# Microcontroller.net
KiCad netlist of a schematic drawn in Altium Designer
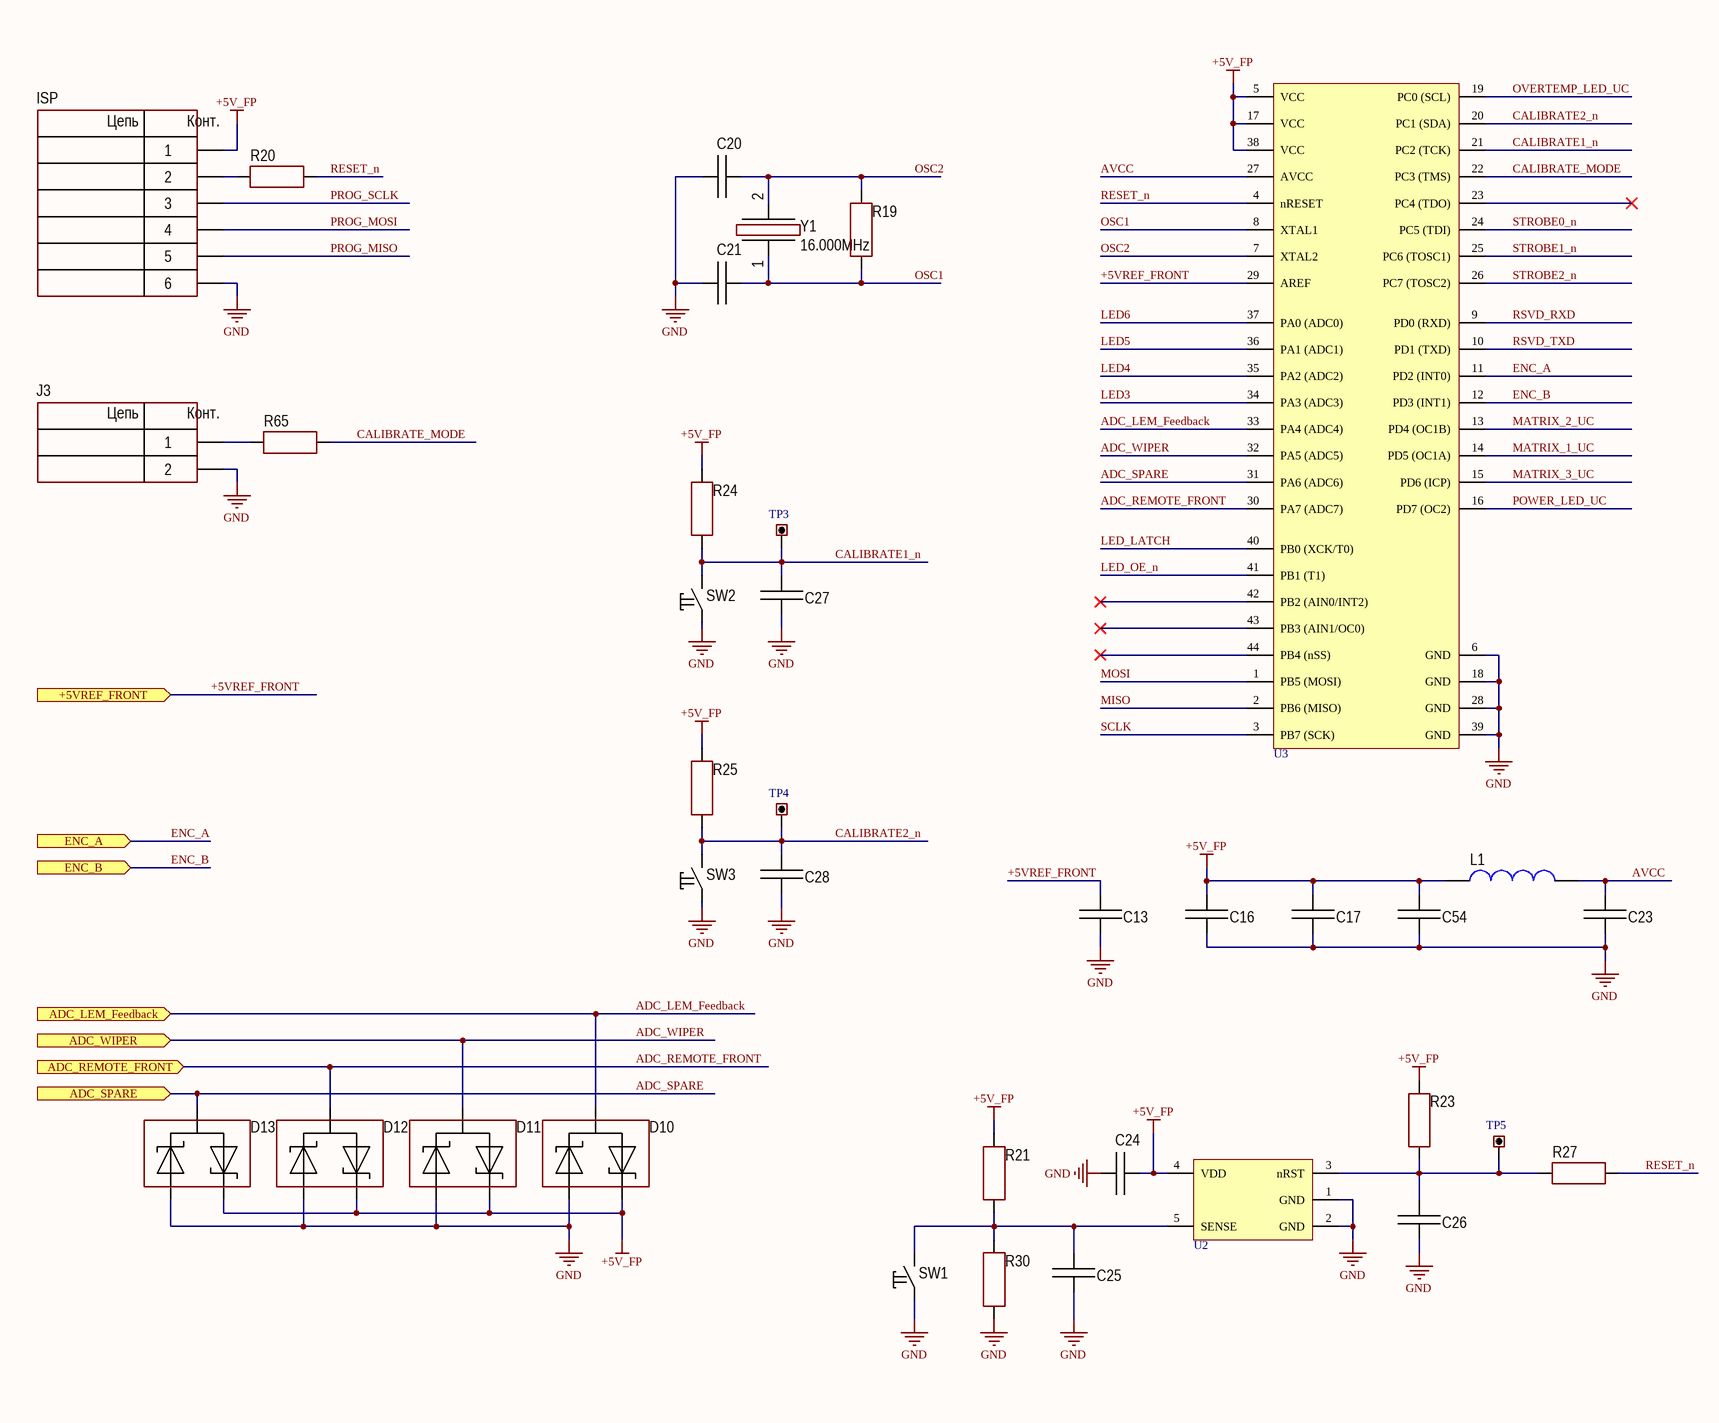
[diagram p0: Microcontroller.SchDoc, left]
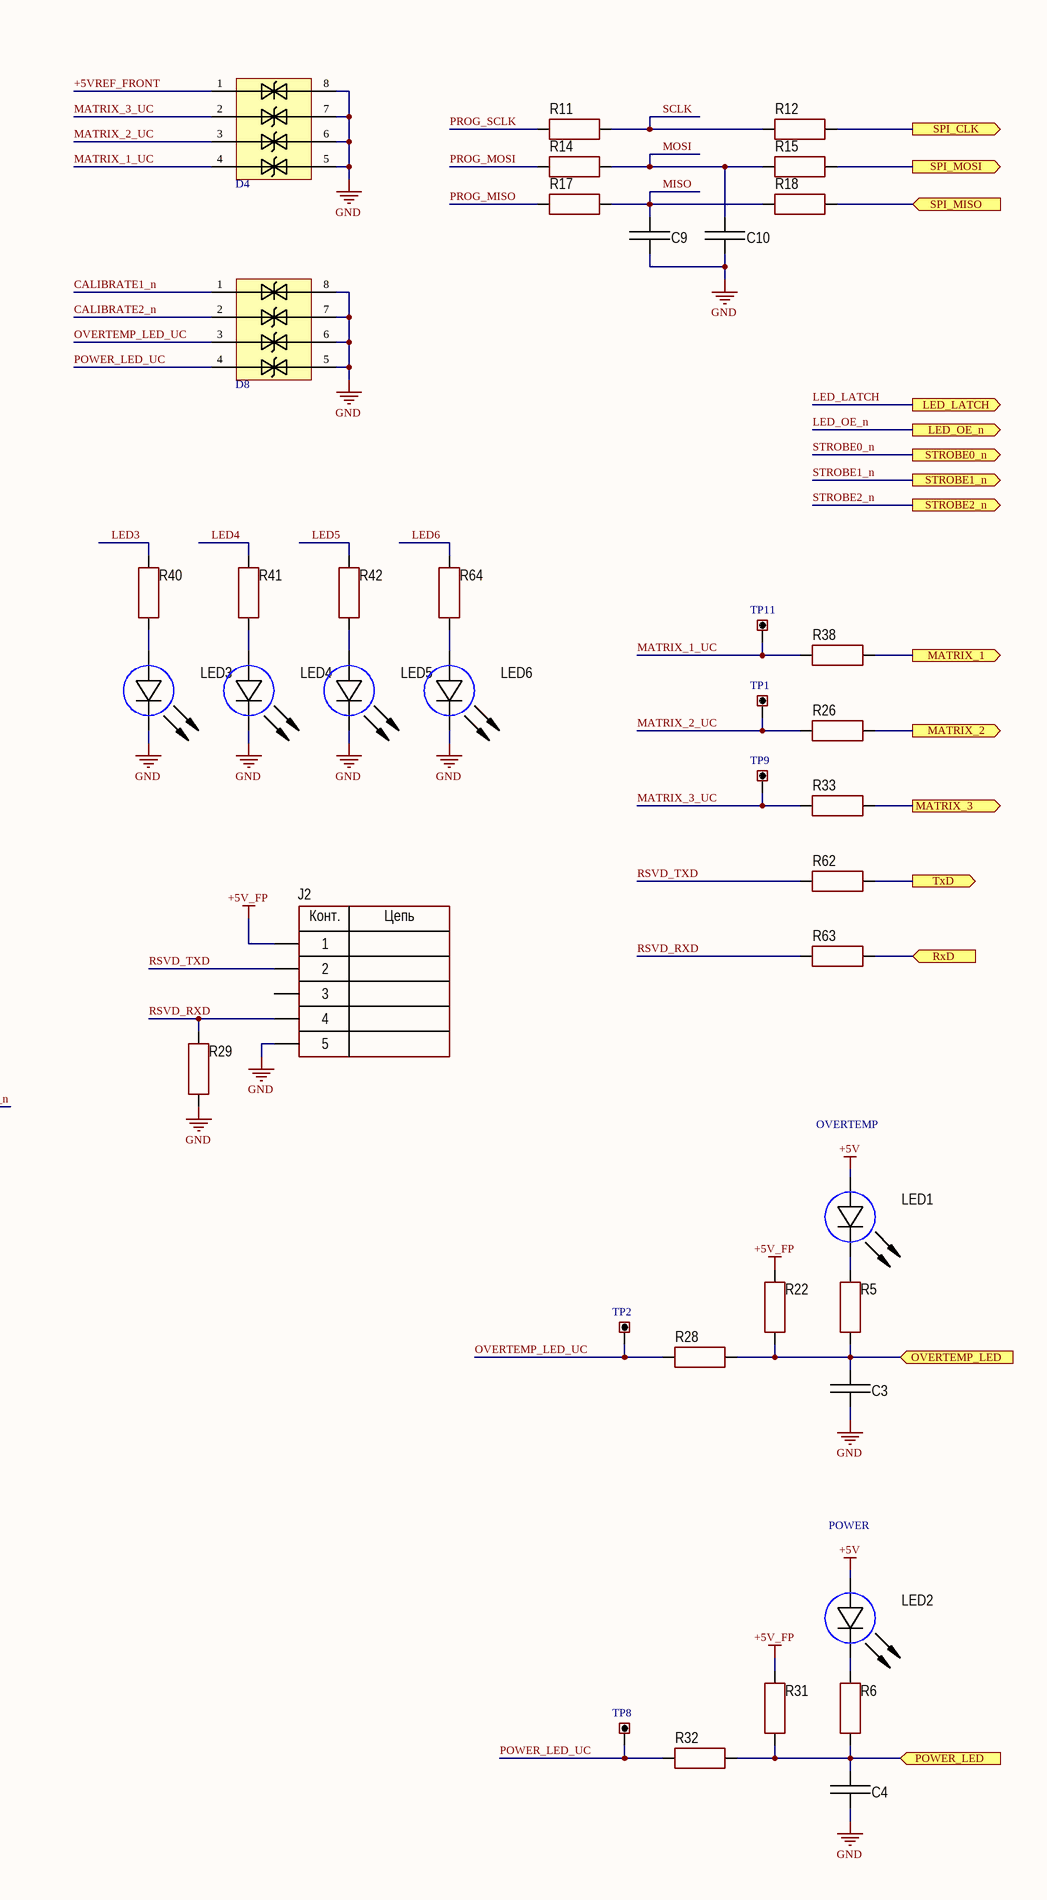
[diagram p1: Microcontroller.SchDoc, right]

(export (version "E")
  (design (tool "Eeschema 10.0.6"))
  (components
    (comp (ref "C3")
      (value "~")
      (footprint "StandardCase:CAP: 1206")
      (fields
        (field (name "MANUFACTURER") "Yageo")
        (field (name "PARTNUMBER") "CC1206KRX7R9BB104")
        (field (name "VALUEMANUFACTURERPARTNUMBER") "Ceramic capacitor, 0.1μF, 1206")
      )
      (libsource (lib "Capacitor") (part "Ceramic_1206"))
    )
    (comp (ref "C4")
      (value "~")
      (footprint "StandardCase:CAP: 1206")
      (fields
        (field (name "MANUFACTURER") "Yageo")
        (field (name "PARTNUMBER") "CC1206KRX7R9BB104")
        (field (name "VALUEMANUFACTURERPARTNUMBER") "Ceramic capacitor, 0.1μF, 1206")
      )
      (libsource (lib "Capacitor") (part "Ceramic_1206"))
    )
    (comp (ref "C9")
      (value "~")
      (footprint "StandardCase:CAP: 1206")
      (fields
        (field (name "MANUFACTURER") "Yageo")
        (field (name "PARTNUMBER") "CC1206KRX7R9BB104")
        (field (name "VALUEMANUFACTURERPARTNUMBER") "Ceramic capacitor, 10nF, 1206")
      )
      (libsource (lib "Capacitor") (part "Ceramic_1206"))
    )
    (comp (ref "C10")
      (value "~")
      (footprint "StandardCase:CAP: 1206")
      (fields
        (field (name "MANUFACTURER") "Yageo")
        (field (name "PARTNUMBER") "CC1206KRX7R9BB104")
        (field (name "VALUEMANUFACTURERPARTNUMBER") "Ceramic capacitor, 10nF, 1206")
      )
      (libsource (lib "Capacitor") (part "Ceramic_1206"))
    )
    (comp (ref "C13")
      (value "~")
      (footprint "StandardCase:CAP: 1206")
      (fields
        (field (name "MANUFACTURER") "Yageo")
        (field (name "PARTNUMBER") "CC1206KRX7R9BB104")
        (field (name "VALUEMANUFACTURERPARTNUMBER") "Ceramic capacitor, 0.1μF, 1206")
      )
      (libsource (lib "Capacitor") (part "Ceramic_1206"))
    )
    (comp (ref "C16")
      (value "~")
      (footprint "StandardCase:CAP: 1206")
      (fields
        (field (name "MANUFACTURER") "Yageo")
        (field (name "PARTNUMBER") "CC1206KRX7R9BB104")
        (field (name "VALUEMANUFACTURERPARTNUMBER") "Ceramic capacitor, 0.1μF, 1206")
      )
      (libsource (lib "Capacitor") (part "Ceramic_1206"))
    )
    (comp (ref "C17")
      (value "~")
      (footprint "StandardCase:CAP: 1206")
      (fields
        (field (name "MANUFACTURER") "Yageo")
        (field (name "PARTNUMBER") "CC1206KRX7R9BB104")
        (field (name "VALUEMANUFACTURERPARTNUMBER") "Ceramic capacitor, 0.1μF, 1206")
      )
      (libsource (lib "Capacitor") (part "Ceramic_1206"))
    )
    (comp (ref "C20")
      (value "~")
      (footprint "StandardCase:CAP: 1206")
      (fields
        (field (name "MANUFACTURER") "Yageo")
        (field (name "PARTNUMBER") "CC1206KRX7R9BB104")
        (field (name "VALUEMANUFACTURERPARTNUMBER") "Ceramic capacitor, 22pF, 1206")
      )
      (libsource (lib "Capacitor") (part "Ceramic_1206"))
    )
    (comp (ref "C21")
      (value "~")
      (footprint "StandardCase:CAP: 1206")
      (fields
        (field (name "MANUFACTURER") "Yageo")
        (field (name "PARTNUMBER") "CC1206KRX7R9BB104")
        (field (name "VALUEMANUFACTURERPARTNUMBER") "Ceramic capacitor, 22pF, 1206")
      )
      (libsource (lib "Capacitor") (part "Ceramic_1206"))
    )
    (comp (ref "C23")
      (value "~")
      (footprint "StandardCase:CAP: 1206")
      (fields
        (field (name "MANUFACTURER") "Yageo")
        (field (name "PARTNUMBER") "CC1206KRX7R9BB104")
        (field (name "VALUEMANUFACTURERPARTNUMBER") "Ceramic capacitor, 1.0μF, 1206")
      )
      (libsource (lib "Capacitor") (part "Ceramic_1206"))
    )
    (comp (ref "C24")
      (value "~")
      (footprint "StandardCase:CAP: 1206")
      (fields
        (field (name "MANUFACTURER") "Yageo")
        (field (name "PARTNUMBER") "CC1206KRX7R9BB104")
        (field (name "VALUEMANUFACTURERPARTNUMBER") "Ceramic capacitor, 10nF, 1206")
      )
      (libsource (lib "Capacitor") (part "Ceramic_1206"))
    )
    (comp (ref "C25")
      (value "~")
      (footprint "StandardCase:CAP: 1206")
      (fields
        (field (name "MANUFACTURER") "Yageo")
        (field (name "PARTNUMBER") "CC1206KRX7R9BB104")
        (field (name "VALUEMANUFACTURERPARTNUMBER") "Ceramic capacitor, 10nF, 1206")
      )
      (libsource (lib "Capacitor") (part "Ceramic_1206"))
    )
    (comp (ref "C26")
      (value "~")
      (footprint "StandardCase:CAP: 1206")
      (fields
        (field (name "MANUFACTURER") "Yageo")
        (field (name "PARTNUMBER") "CC1206KRX7R9BB104")
        (field (name "VALUEMANUFACTURERPARTNUMBER") "Ceramic capacitor, 0.1μF, 1206")
      )
      (libsource (lib "Capacitor") (part "Ceramic_1206"))
    )
    (comp (ref "C27")
      (value "~")
      (footprint "StandardCase:CAP: 1206")
      (fields
        (field (name "MANUFACTURER") "Yageo")
        (field (name "PARTNUMBER") "CC1206KRX7R9BB104")
        (field (name "VALUEMANUFACTURERPARTNUMBER") "Ceramic capacitor, 0.1μF, 1206")
      )
      (libsource (lib "Capacitor") (part "Ceramic_1206"))
    )
    (comp (ref "C28")
      (value "~")
      (footprint "StandardCase:CAP: 1206")
      (fields
        (field (name "MANUFACTURER") "Yageo")
        (field (name "PARTNUMBER") "CC1206KRX7R9BB104")
        (field (name "VALUEMANUFACTURERPARTNUMBER") "Ceramic capacitor, 0.1μF, 1206")
      )
      (libsource (lib "Capacitor") (part "Ceramic_1206"))
    )
    (comp (ref "C54")
      (value "~")
      (footprint "StandardCase:CAP: 1206")
      (fields
        (field (name "MANUFACTURER") "Yageo")
        (field (name "PARTNUMBER") "CC1206KRX7R9BB104")
        (field (name "VALUEMANUFACTURERPARTNUMBER") "Ceramic capacitor, 0.1μF, 1206")
      )
      (libsource (lib "Capacitor") (part "Ceramic_1206"))
    )
    (comp (ref "D4")
      (value "~")
      (footprint "StandardCase:8-SOIC")
      (fields
        (field (name "VALUEMANUFACTURERPARTNUMBER") "CDNBS08-T05C, SOIC-8")
        (field (name "PARTNUMBER") "CDNBS08-T05C")
      )
      (libsource (lib "FP_lib_SCH") (part "CDNBS08-T05C"))
    )
    (comp (ref "D8")
      (value "~")
      (footprint "StandardCase:8-SOIC")
      (fields
        (field (name "VALUEMANUFACTURERPARTNUMBER") "CDNBS08-T05C, SOIC-8")
        (field (name "PARTNUMBER") "CDNBS08-T05C")
      )
      (libsource (lib "FP_lib_SCH") (part "CDNBS08-T05C"))
    )
    (comp (ref "D10")
      (value "~")
      (footprint "StandardCase:SOT23")
      (fields
        (field (name "MANUFACTURER") "Diodes Incorporated")
        (field (name "VALUEMANUFACTURERPARTNUMBER") "BAS40-04, SOT23-3")
        (field (name "VOLTAGE") "40V")
      )
      (libsource (lib "Diode") (part "Schottky_array"))
    )
    (comp (ref "D11")
      (value "~")
      (footprint "StandardCase:SOT23")
      (fields
        (field (name "MANUFACTURER") "Diodes Incorporated")
        (field (name "VALUEMANUFACTURERPARTNUMBER") "BAS40-04, SOT23-3")
        (field (name "VOLTAGE") "40V")
      )
      (libsource (lib "Diode") (part "Schottky_array"))
    )
    (comp (ref "D12")
      (value "~")
      (footprint "StandardCase:SOT23")
      (fields
        (field (name "MANUFACTURER") "Diodes Incorporated")
        (field (name "VALUEMANUFACTURERPARTNUMBER") "BAS40-04, SOT23-3")
        (field (name "VOLTAGE") "40V")
      )
      (libsource (lib "Diode") (part "Schottky_array"))
    )
    (comp (ref "D13")
      (value "~")
      (footprint "StandardCase:SOT23")
      (fields
        (field (name "MANUFACTURER") "Diodes Incorporated")
        (field (name "VALUEMANUFACTURERPARTNUMBER") "BAS40-04, SOT23-3")
        (field (name "VOLTAGE") "40V")
      )
      (libsource (lib "Diode") (part "Schottky_array"))
    )
    (comp (ref "ISP")
      (value "~")
      (footprint "CustomCase:CON: PLS-6")
      (fields
        (field (name "MANUFACTURER") "Connfly")
        (field (name "VALUEMANUFACTURERPARTNUMBER") "Connector, PLS-6, 6 pin")
        (field (name "PARTNUMBER") "PLS-6")
      )
      (libsource (lib "Connector") (part "PLS-6"))
    )
    (comp (ref "J2")
      (value "~")
      (footprint "CustomCase:CON: PLS-5")
      (fields
        (field (name "MANUFACTURER") "Connfly")
        (field (name "VALUEMANUFACTURERPARTNUMBER") "Connector, PBS-5, 5 pin")
        (field (name "PARTNUMBER") "PBS-5")
      )
      (libsource (lib "Connector") (part "PBS-5"))
    )
    (comp (ref "J3")
      (value "~")
      (footprint "CustomCase:CON: PLS-2")
      (fields
        (field (name "MANUFACTURER") "Connfly")
        (field (name "VALUEMANUFACTURERPARTNUMBER") "PLS-2, 2pin")
        (field (name "PARTNUMBER") "PLS-2")
      )
      (libsource (lib "Connector") (part "PLS-2"))
    )
    (comp (ref "L1")
      (value "~")
      (footprint "StandardCase:RES: 1206")
      (fields
        (field (name "MANUFACTURER") "Murata Electronics")
        (field (name "PARTNUMBER") "LQM21FN100M70L")
        (field (name "VALUEMANUFACTURERPARTNUMBER") "Fixed inductor, 100μH, 1206")
      )
      (libsource (lib "Inductor") (part "Inductor_0805"))
    )
    (comp (ref "LED1")
      (value "~")
      (footprint "CustomCase:DIODE: LED5MM_Y")
      (fields (field (name "VALUEMANUFACTURERPARTNUMBER") "LED, YELLOW, 5 mm"))
      (libsource (lib "Diode") (part "LED_single"))
    )
    (comp (ref "LED2")
      (value "~")
      (footprint "CustomCase:DIODE: LED5MM_G")
      (fields (field (name "VALUEMANUFACTURERPARTNUMBER") "LED, BLUE, 5 mm"))
      (libsource (lib "Diode") (part "LED_single"))
    )
    (comp (ref "LED3")
      (value "~")
      (footprint "CustomCase:DIODE: LED5MM_G")
      (fields (field (name "VALUEMANUFACTURERPARTNUMBER") "LED, GREEN, 5 mm"))
      (libsource (lib "Diode") (part "LED_single"))
    )
    (comp (ref "LED4")
      (value "~")
      (footprint "CustomCase:DIODE: LED5MM_G")
      (fields (field (name "VALUEMANUFACTURERPARTNUMBER") "LED, GREEN, 5 mm"))
      (libsource (lib "Diode") (part "LED_single"))
    )
    (comp (ref "LED5")
      (value "~")
      (footprint "CustomCase:DIODE: LED5MM_G")
      (fields (field (name "VALUEMANUFACTURERPARTNUMBER") "LED, GREEN, 5 mm"))
      (libsource (lib "Diode") (part "LED_single"))
    )
    (comp (ref "LED6")
      (value "~")
      (footprint "CustomCase:DIODE: LED5MM_G")
      (fields (field (name "VALUEMANUFACTURERPARTNUMBER") "LED, GREEN, 5 mm"))
      (libsource (lib "Diode") (part "LED_single"))
    )
    (comp (ref "R5")
      (value "~")
      (footprint "StandardCase:RES: 1206")
      (fields
        (field (name "MANUFACTURER") "Yageo")
        (field (name "PARTNUMBER") "RC1206JR-07100RL")
        (field (name "VALUEMANUFACTURERPARTNUMBER") "Resistor, 2K, 1206")
      )
      (libsource (lib "") (part "Resistor_1206_2"))
    )
    (comp (ref "R6")
      (value "~")
      (footprint "StandardCase:RES: 1206")
      (fields
        (field (name "MANUFACTURER") "Yageo")
        (field (name "PARTNUMBER") "RC1206JR-07100RL")
        (field (name "VALUEMANUFACTURERPARTNUMBER") "Resistor, 2K, 1206")
      )
      (libsource (lib "") (part "Resistor_1206_2"))
    )
    (comp (ref "R11")
      (value "~")
      (footprint "StandardCase:RES: 1206")
      (fields
        (field (name "MANUFACTURER") "Yageo")
        (field (name "PARTNUMBER") "RC1206JR-07100RL")
        (field (name "VALUEMANUFACTURERPARTNUMBER") "Resistor, 47R, 1206")
      )
      (libsource (lib "Resistor") (part "Resistor_1206"))
    )
    (comp (ref "R12")
      (value "~")
      (footprint "StandardCase:RES: 1206")
      (fields
        (field (name "MANUFACTURER") "Yageo")
        (field (name "PARTNUMBER") "RC1206JR-07100RL")
        (field (name "VALUEMANUFACTURERPARTNUMBER") "Resistor, 47R, 1206")
      )
      (libsource (lib "Resistor") (part "Resistor_1206"))
    )
    (comp (ref "R14")
      (value "~")
      (footprint "StandardCase:RES: 1206")
      (fields
        (field (name "MANUFACTURER") "Yageo")
        (field (name "PARTNUMBER") "RC1206JR-07100RL")
        (field (name "VALUEMANUFACTURERPARTNUMBER") "Resistor, 47R, 1206")
      )
      (libsource (lib "Resistor") (part "Resistor_1206"))
    )
    (comp (ref "R15")
      (value "~")
      (footprint "StandardCase:RES: 1206")
      (fields
        (field (name "MANUFACTURER") "Yageo")
        (field (name "PARTNUMBER") "RC1206JR-07100RL")
        (field (name "VALUEMANUFACTURERPARTNUMBER") "Resistor, 47R, 1206")
      )
      (libsource (lib "Resistor") (part "Resistor_1206"))
    )
    (comp (ref "R17")
      (value "~")
      (footprint "StandardCase:RES: 1206")
      (fields
        (field (name "MANUFACTURER") "Yageo")
        (field (name "PARTNUMBER") "RC1206JR-07100RL")
        (field (name "VALUEMANUFACTURERPARTNUMBER") "Resistor, 47R, 1206")
      )
      (libsource (lib "Resistor") (part "Resistor_1206"))
    )
    (comp (ref "R18")
      (value "~")
      (footprint "StandardCase:RES: 1206")
      (fields
        (field (name "MANUFACTURER") "Yageo")
        (field (name "PARTNUMBER") "RC1206JR-07100RL")
        (field (name "VALUEMANUFACTURERPARTNUMBER") "Resistor, 47R, 1206")
      )
      (libsource (lib "Resistor") (part "Resistor_1206"))
    )
    (comp (ref "R19")
      (value "~")
      (footprint "StandardCase:RES: 1206")
      (fields
        (field (name "MANUFACTURER") "Yageo")
        (field (name "PARTNUMBER") "RC1206JR-07100RL")
        (field (name "VALUEMANUFACTURERPARTNUMBER") "Resistor, 1M, 1206")
      )
      (libsource (lib "") (part "Resistor_1206_1"))
    )
    (comp (ref "R20")
      (value "~")
      (footprint "StandardCase:RES: 1206")
      (fields
        (field (name "MANUFACTURER") "Yageo")
        (field (name "PARTNUMBER") "RC1206JR-07100RL")
        (field (name "VALUEMANUFACTURERPARTNUMBER") "Resistor, 47R, 1206")
      )
      (libsource (lib "Resistor") (part "Resistor_1206"))
    )
    (comp (ref "R21")
      (value "~")
      (footprint "StandardCase:RES: 1206")
      (fields
        (field (name "MANUFACTURER") "Yageo")
        (field (name "PARTNUMBER") "RC1206JR-07100RL")
        (field (name "VALUEMANUFACTURERPARTNUMBER") "Resistor, 10K, 1206")
      )
      (libsource (lib "") (part "Resistor_1206_1"))
    )
    (comp (ref "R22")
      (value "~")
      (footprint "StandardCase:RES: 1206")
      (fields
        (field (name "MANUFACTURER") "Yageo")
        (field (name "PARTNUMBER") "RC1206JR-07100RL")
        (field (name "VALUEMANUFACTURERPARTNUMBER") "Resistor, 10K, 1206")
      )
      (libsource (lib "") (part "Resistor_1206_2"))
    )
    (comp (ref "R23")
      (value "~")
      (footprint "StandardCase:RES: 1206")
      (fields
        (field (name "MANUFACTURER") "Yageo")
        (field (name "PARTNUMBER") "RC1206JR-07100RL")
        (field (name "VALUEMANUFACTURERPARTNUMBER") "Resistor, 10K, 1206")
      )
      (libsource (lib "") (part "Resistor_1206_1"))
    )
    (comp (ref "R24")
      (value "~")
      (footprint "StandardCase:RES: 1206")
      (fields
        (field (name "MANUFACTURER") "Yageo")
        (field (name "PARTNUMBER") "RC1206JR-07100RL")
        (field (name "VALUEMANUFACTURERPARTNUMBER") "Resistor, 10K, 1206")
      )
      (libsource (lib "") (part "Resistor_1206_1"))
    )
    (comp (ref "R25")
      (value "~")
      (footprint "StandardCase:RES: 1206")
      (fields
        (field (name "MANUFACTURER") "Yageo")
        (field (name "PARTNUMBER") "RC1206JR-07100RL")
        (field (name "VALUEMANUFACTURERPARTNUMBER") "Resistor, 10K, 1206")
      )
      (libsource (lib "") (part "Resistor_1206_1"))
    )
    (comp (ref "R26")
      (value "~")
      (footprint "StandardCase:RES: 1206")
      (fields
        (field (name "MANUFACTURER") "Yageo")
        (field (name "PARTNUMBER") "RC1206JR-07100RL")
        (field (name "VALUEMANUFACTURERPARTNUMBER") "Resistor, 1K, 1206")
      )
      (libsource (lib "") (part "Resistor_1206_3"))
    )
    (comp (ref "R27")
      (value "~")
      (footprint "StandardCase:RES: 1206")
      (fields
        (field (name "MANUFACTURER") "Yageo")
        (field (name "PARTNUMBER") "RC1206JR-07100RL")
        (field (name "VALUEMANUFACTURERPARTNUMBER") "Resistor, 47R, 1206")
      )
      (libsource (lib "Resistor") (part "Resistor_1206"))
    )
    (comp (ref "R28")
      (value "~")
      (footprint "StandardCase:RES: 1206")
      (fields
        (field (name "MANUFACTURER") "Yageo")
        (field (name "PARTNUMBER") "RC1206JR-07100RL")
        (field (name "VALUEMANUFACTURERPARTNUMBER") "Resistor, 1K, 1206")
      )
      (libsource (lib "Resistor") (part "Resistor_1206"))
    )
    (comp (ref "R29")
      (value "~")
      (footprint "StandardCase:RES: 1206")
      (fields
        (field (name "MANUFACTURER") "Yageo")
        (field (name "PARTNUMBER") "RC1206JR-07100RL")
        (field (name "VALUEMANUFACTURERPARTNUMBER") "Resistor, 10K, 1206")
      )
      (libsource (lib "") (part "Resistor_1206_1"))
    )
    (comp (ref "R30")
      (value "~")
      (footprint "StandardCase:RES: 1206")
      (fields
        (field (name "MANUFACTURER") "Yageo")
        (field (name "PARTNUMBER") "RC1206JR-07100RL")
        (field (name "VALUEMANUFACTURERPARTNUMBER") "Resistor, 4.32K, 1206")
      )
      (libsource (lib "") (part "Resistor_1206_1"))
    )
    (comp (ref "R31")
      (value "~")
      (footprint "StandardCase:RES: 1206")
      (fields
        (field (name "MANUFACTURER") "Yageo")
        (field (name "PARTNUMBER") "RC1206JR-07100RL")
        (field (name "VALUEMANUFACTURERPARTNUMBER") "Resistor, 10K, 1206")
      )
      (libsource (lib "") (part "Resistor_1206_2"))
    )
    (comp (ref "R32")
      (value "~")
      (footprint "StandardCase:RES: 1206")
      (fields
        (field (name "MANUFACTURER") "Yageo")
        (field (name "PARTNUMBER") "RC1206JR-07100RL")
        (field (name "VALUEMANUFACTURERPARTNUMBER") "Resistor, 1K, 1206")
      )
      (libsource (lib "") (part "Resistor_1206_3"))
    )
    (comp (ref "R33")
      (value "~")
      (footprint "StandardCase:RES: 1206")
      (fields
        (field (name "MANUFACTURER") "Yageo")
        (field (name "PARTNUMBER") "RC1206JR-07100RL")
        (field (name "VALUEMANUFACTURERPARTNUMBER") "Resistor, 1K, 1206")
      )
      (libsource (lib "") (part "Resistor_1206_3"))
    )
    (comp (ref "R38")
      (value "~")
      (footprint "StandardCase:RES: 1206")
      (fields
        (field (name "MANUFACTURER") "Yageo")
        (field (name "PARTNUMBER") "RC1206JR-07100RL")
        (field (name "VALUEMANUFACTURERPARTNUMBER") "Resistor, 1K, 1206")
      )
      (libsource (lib "") (part "Resistor_1206_3"))
    )
    (comp (ref "R40")
      (value "~")
      (footprint "StandardCase:RES: 1206")
      (fields
        (field (name "MANUFACTURER") "Yageo")
        (field (name "PARTNUMBER") "RC1206JR-07100RL")
        (field (name "VALUEMANUFACTURERPARTNUMBER") "Resistor, 2K, 1206")
      )
      (libsource (lib "") (part "Resistor_1206_2"))
    )
    (comp (ref "R41")
      (value "~")
      (footprint "StandardCase:RES: 1206")
      (fields
        (field (name "MANUFACTURER") "Yageo")
        (field (name "PARTNUMBER") "RC1206JR-07100RL")
        (field (name "VALUEMANUFACTURERPARTNUMBER") "Resistor, 2K, 1206")
      )
      (libsource (lib "") (part "Resistor_1206_2"))
    )
    (comp (ref "R42")
      (value "~")
      (footprint "StandardCase:RES: 1206")
      (fields
        (field (name "MANUFACTURER") "Yageo")
        (field (name "PARTNUMBER") "RC1206JR-07100RL")
        (field (name "VALUEMANUFACTURERPARTNUMBER") "Resistor, 2K, 1206")
      )
      (libsource (lib "") (part "Resistor_1206_2"))
    )
    (comp (ref "R62")
      (value "~")
      (footprint "StandardCase:RES: 1206")
      (fields
        (field (name "MANUFACTURER") "Yageo")
        (field (name "PARTNUMBER") "RC1206JR-07100RL")
        (field (name "VALUEMANUFACTURERPARTNUMBER") "Resistor, 1K, 1206")
      )
      (libsource (lib "") (part "Resistor_1206_3"))
    )
    (comp (ref "R63")
      (value "~")
      (footprint "StandardCase:RES: 1206")
      (fields
        (field (name "MANUFACTURER") "Yageo")
        (field (name "PARTNUMBER") "RC1206JR-07100RL")
        (field (name "VALUEMANUFACTURERPARTNUMBER") "Resistor, 1K, 1206")
      )
      (libsource (lib "") (part "Resistor_1206_3"))
    )
    (comp (ref "R64")
      (value "~")
      (footprint "StandardCase:RES: 1206")
      (fields
        (field (name "MANUFACTURER") "Yageo")
        (field (name "PARTNUMBER") "RC1206JR-07100RL")
        (field (name "VALUEMANUFACTURERPARTNUMBER") "Resistor, 2K, 1206")
      )
      (libsource (lib "") (part "Resistor_1206_2"))
    )
    (comp (ref "R65")
      (value "~")
      (footprint "StandardCase:RES: 1206")
      (fields
        (field (name "MANUFACTURER") "Yageo")
        (field (name "PARTNUMBER") "RC1206JR-07100RL")
        (field (name "VALUEMANUFACTURERPARTNUMBER") "Resistor, 1K, 1206")
      )
      (libsource (lib "Resistor") (part "Resistor_1206"))
    )
    (comp (ref "SW1")
      (value "~")
      (footprint "FP_lib_PCB:DTSM-32")
      (fields
        (field (name "MANUFACTURER") "TE Connectivity")
        (field (name "VALUEMANUFACTURERPARTNUMBER") "Tactile button, DTSM-32")
        (field (name "PARTNUMBER") "DTSM-32")
      )
      (libsource (lib "Electromechanics") (part "Button_tactile"))
    )
    (comp (ref "SW2")
      (value "~")
      (footprint "FP_lib_PCB:DTSM-32")
      (fields
        (field (name "MANUFACTURER") "TE Connectivity")
        (field (name "VALUEMANUFACTURERPARTNUMBER") "Tactile button, DTSM-32")
        (field (name "PARTNUMBER") "DTSM-32")
      )
      (libsource (lib "Electromechanics") (part "Button_tactile"))
    )
    (comp (ref "SW3")
      (value "~")
      (footprint "FP_lib_PCB:DTSM-32")
      (fields
        (field (name "MANUFACTURER") "TE Connectivity")
        (field (name "VALUEMANUFACTURERPARTNUMBER") "Tactile button, DTSM-32")
        (field (name "PARTNUMBER") "DTSM-32")
      )
      (libsource (lib "Electromechanics") (part "Button_tactile"))
    )
    (comp (ref "TP1")
      (value "Test_Point")
      (footprint "FP_lib_PCB:Test_Point")
      (libsource (lib "FP_lib_SCH") (part "Test_Point"))
    )
    (comp (ref "TP2")
      (value "Test_Point")
      (footprint "FP_lib_PCB:Test_Point")
      (libsource (lib "FP_lib_SCH") (part "Test_Point"))
    )
    (comp (ref "TP3")
      (value "Test_Point")
      (footprint "FP_lib_PCB:Test_Point")
      (libsource (lib "FP_lib_SCH") (part "Test_Point"))
    )
    (comp (ref "TP4")
      (value "Test_Point")
      (footprint "FP_lib_PCB:Test_Point")
      (libsource (lib "FP_lib_SCH") (part "Test_Point"))
    )
    (comp (ref "TP5")
      (value "Test_Point")
      (footprint "FP_lib_PCB:Test_Point")
      (libsource (lib "FP_lib_SCH") (part "Test_Point"))
    )
    (comp (ref "TP8")
      (value "Test_Point")
      (footprint "FP_lib_PCB:Test_Point")
      (libsource (lib "FP_lib_SCH") (part "Test_Point"))
    )
    (comp (ref "TP9")
      (value "Test_Point")
      (footprint "FP_lib_PCB:Test_Point")
      (libsource (lib "FP_lib_SCH") (part "Test_Point"))
    )
    (comp (ref "TP11")
      (value "Test_Point")
      (footprint "FP_lib_PCB:Test_Point")
      (libsource (lib "FP_lib_SCH") (part "Test_Point"))
    )
    (comp (ref "U2")
      (value "~")
      (footprint "FP_lib_PCB:TPS3801")
      (fields
        (field (name "VALUEMANUFACTURERPARTNUMBER") "TPS3801, SOT23-5")
        (field (name "PARTNUMBER") "TPS3801")
      )
      (libsource (lib "FP_lib_SCH") (part "TPS3801"))
    )
    (comp (ref "U3")
      (value "~")
      (footprint "FP_lib_PCB:TQFP80P1200X1200X120-44L")
      (fields
        (field (name "VALUEMANUFACTURERPARTNUMBER") "ATMega16-16AU, TQFP-44")
        (field (name "PARTNUMBER") "ATMega16-16AU")
      )
      (libsource (lib "FP_lib_SCH") (part "ATMega16-16AU"))
    )
    (comp (ref "Y1")
      (value "~")
      (footprint "FP_lib_PCB:HC49SM")
      (fields
        (field (name "MANUFACTURER") "Epson")
        (field (name "PARTNUMBER") "HC49SM-16.000MHZ-20PF")
        (field (name "VALUEMANUFACTURERPARTNUMBER") "HC49SM-16.000MHZ-20PF, HC49SM")
        (field (name "FREQUENCY") "16.000MHz")
      )
      (libsource (lib "Oscilator") (part "Crystal_3215"))
    )
  )
  (nets
    (net (code "1") (name "+5V") (class "Default")
      (node (ref "LED1") (pin "1") (pinfunction "A_1") (pintype "passive"))
      (node (ref "LED2") (pin "1") (pinfunction "A_1") (pintype "passive"))
    )
    (net (code "2") (name "+5V_FP") (class "Default")
      (node (ref "C16") (pin "2") (pinfunction "2_2") (pintype "power_in"))
      (node (ref "C17") (pin "2") (pinfunction "2_2") (pintype "power_in"))
      (node (ref "C24") (pin "2") (pinfunction "2_2") (pintype "power_in"))
      (node (ref "C54") (pin "2") (pinfunction "2_2") (pintype "power_in"))
      (node (ref "D10") (pin "2") (pinfunction "2_2") (pintype "passive"))
      (node (ref "D11") (pin "2") (pinfunction "2_2") (pintype "passive"))
      (node (ref "D12") (pin "2") (pinfunction "2_2") (pintype "passive"))
      (node (ref "D13") (pin "2") (pinfunction "2_2") (pintype "passive"))
      (node (ref "ISP") (pin "1") (pinfunction "1_1") (pintype "passive"))
      (node (ref "J2") (pin "1") (pinfunction "1_1") (pintype "passive"))
      (node (ref "L1") (pin "2") (pinfunction "2_2") (pintype "passive"))
      (node (ref "R21") (pin "1") (pinfunction "1_1") (pintype "passive"))
      (node (ref "R22") (pin "2") (pinfunction "2_2") (pintype "passive"))
      (node (ref "R23") (pin "1") (pinfunction "1_1") (pintype "passive"))
      (node (ref "R24") (pin "1") (pinfunction "1_1") (pintype "passive"))
      (node (ref "R25") (pin "1") (pinfunction "1_1") (pintype "passive"))
      (node (ref "R31") (pin "2") (pinfunction "2_2") (pintype "passive"))
      (node (ref "U2") (pin "4") (pinfunction "VDD_4") (pintype "passive"))
      (node (ref "U3") (pin "17") (pinfunction "VCC_17") (pintype "passive"))
      (node (ref "U3") (pin "38") (pinfunction "VCC_38") (pintype "passive"))
      (node (ref "U3") (pin "5") (pinfunction "VCC_5") (pintype "passive"))
    )
    (net (code "3") (name "/+5VREF_FRONT") (class "Default")
      (node (ref "C13") (pin "2") (pinfunction "2_2") (pintype "power_in"))
      (node (ref "D4") (pin "1") (pintype "passive"))
      (node (ref "U3") (pin "29") (pinfunction "AREF_29") (pintype "passive"))
    )
    (net (code "4") (name "/ADC_LEM_Feedback") (class "Default")
      (node (ref "D10") (pin "3") (pinfunction "3_3") (pintype "passive"))
      (node (ref "U3") (pin "33") (pinfunction "PA4_(ADC4)_33") (pintype "passive"))
    )
    (net (code "5") (name "/ADC_REMOTE_FRONT") (class "Default")
      (node (ref "D12") (pin "3") (pinfunction "3_3") (pintype "passive"))
      (node (ref "U3") (pin "30") (pinfunction "PA7_(ADC7)_30") (pintype "passive"))
    )
    (net (code "6") (name "/ADC_SPARE") (class "Default")
      (node (ref "D13") (pin "3") (pinfunction "3_3") (pintype "passive"))
      (node (ref "U3") (pin "31") (pinfunction "PA6_(ADC6)_31") (pintype "passive"))
    )
    (net (code "7") (name "/ADC_WIPER") (class "Default")
      (node (ref "D11") (pin "3") (pinfunction "3_3") (pintype "passive"))
      (node (ref "U3") (pin "32") (pinfunction "PA5_(ADC5)_32") (pintype "passive"))
    )
    (net (code "8") (name "/AVCC") (class "Default")
      (node (ref "C23") (pin "2") (pinfunction "2_2") (pintype "power_in"))
      (node (ref "L1") (pin "1") (pinfunction "1_1") (pintype "passive"))
      (node (ref "U3") (pin "27") (pinfunction "AVCC_27") (pintype "passive"))
    )
    (net (code "9") (name "/CALIBRATE1_n") (class "Default")
      (node (ref "C27") (pin "2") (pinfunction "2_2") (pintype "power_in"))
      (node (ref "D8") (pin "1") (pintype "passive"))
      (node (ref "R24") (pin "2") (pinfunction "2_2") (pintype "passive"))
      (node (ref "SW2") (pin "2") (pinfunction "2_2") (pintype "passive"))
      (node (ref "TP3") (pin "1") (pinfunction "1_1") (pintype "passive"))
      (node (ref "U3") (pin "21") (pinfunction "PC2_(TCK)_21") (pintype "passive"))
    )
    (net (code "10") (name "/CALIBRATE2_n") (class "Default")
      (node (ref "C28") (pin "2") (pinfunction "2_2") (pintype "power_in"))
      (node (ref "D8") (pin "2") (pintype "passive"))
      (node (ref "R25") (pin "2") (pinfunction "2_2") (pintype "passive"))
      (node (ref "SW3") (pin "2") (pinfunction "2_2") (pintype "passive"))
      (node (ref "TP4") (pin "1") (pinfunction "1_1") (pintype "passive"))
      (node (ref "U3") (pin "20") (pinfunction "PC1_(SDA)_20") (pintype "passive"))
    )
    (net (code "11") (name "/CALIBRATE_MODE") (class "Default")
      (node (ref "R65") (pin "1") (pinfunction "1_1") (pintype "passive"))
      (node (ref "U3") (pin "22") (pinfunction "PC3_(TMS)_22") (pintype "passive"))
    )
    (net (code "12") (name "/ENC_A") (class "Default")
      (node (ref "U3") (pin "11") (pinfunction "PD2_(INT0)_11") (pintype "passive"))
    )
    (net (code "13") (name "/ENC_B") (class "Default")
      (node (ref "U3") (pin "12") (pinfunction "PD3_(INT1)_12") (pintype "passive"))
    )
    (net (code "14") (name "/LED3") (class "Default")
      (node (ref "R40") (pin "2") (pinfunction "2_2") (pintype "passive"))
      (node (ref "U3") (pin "34") (pinfunction "PA3_(ADC3)_34") (pintype "passive"))
    )
    (net (code "15") (name "/LED4") (class "Default")
      (node (ref "R41") (pin "2") (pinfunction "2_2") (pintype "passive"))
      (node (ref "U3") (pin "35") (pinfunction "PA2_(ADC2)_35") (pintype "passive"))
    )
    (net (code "16") (name "/LED5") (class "Default")
      (node (ref "R42") (pin "2") (pinfunction "2_2") (pintype "passive"))
      (node (ref "U3") (pin "36") (pinfunction "PA1_(ADC1)_36") (pintype "passive"))
    )
    (net (code "17") (name "/LED6") (class "Default")
      (node (ref "R64") (pin "2") (pinfunction "2_2") (pintype "passive"))
      (node (ref "U3") (pin "37") (pinfunction "PA0_(ADC0)_37") (pintype "passive"))
    )
    (net (code "18") (name "/LED_LATCH") (class "Default")
      (node (ref "U3") (pin "40") (pinfunction "PB0_(XCK/T0)_40") (pintype "passive"))
    )
    (net (code "19") (name "/LED_OE_n") (class "Default")
      (node (ref "U3") (pin "41") (pinfunction "PB1_(T1)_41") (pintype "passive"))
    )
    (net (code "20") (name "/MATRIX_1") (class "Default")
      (node (ref "R38") (pin "2") (pinfunction "2_2") (pintype "passive"))
    )
    (net (code "21") (name "/MATRIX_1_UC") (class "Default")
      (node (ref "D4") (pin "4") (pintype "passive"))
      (node (ref "R38") (pin "1") (pinfunction "1_1") (pintype "passive"))
      (node (ref "TP11") (pin "1") (pinfunction "1_1") (pintype "passive"))
      (node (ref "U3") (pin "14") (pinfunction "PD5_(OC1A)_14") (pintype "passive"))
    )
    (net (code "22") (name "/MATRIX_2") (class "Default")
      (node (ref "R26") (pin "2") (pinfunction "2_2") (pintype "passive"))
    )
    (net (code "23") (name "/MATRIX_2_UC") (class "Default")
      (node (ref "D4") (pin "3") (pintype "passive"))
      (node (ref "R26") (pin "1") (pinfunction "1_1") (pintype "passive"))
      (node (ref "TP1") (pin "1") (pinfunction "1_1") (pintype "passive"))
      (node (ref "U3") (pin "13") (pinfunction "PD4_(OC1B)_13") (pintype "passive"))
    )
    (net (code "24") (name "/MATRIX_3") (class "Default")
      (node (ref "R33") (pin "2") (pinfunction "2_2") (pintype "passive"))
    )
    (net (code "25") (name "/MATRIX_3_UC") (class "Default")
      (node (ref "D4") (pin "2") (pintype "passive"))
      (node (ref "R33") (pin "1") (pinfunction "1_1") (pintype "passive"))
      (node (ref "TP9") (pin "1") (pinfunction "1_1") (pintype "passive"))
      (node (ref "U3") (pin "15") (pinfunction "PD6_(ICP)_15") (pintype "passive"))
    )
    (net (code "26") (name "/MISO") (class "Default")
      (node (ref "C9") (pin "2") (pinfunction "2_2") (pintype "power_in"))
      (node (ref "R17") (pin "1") (pinfunction "1_1") (pintype "passive"))
      (node (ref "R18") (pin "2") (pinfunction "2_2") (pintype "passive"))
      (node (ref "U3") (pin "2") (pinfunction "PB6_(MISO)_2") (pintype "passive"))
    )
    (net (code "27") (name "/MOSI") (class "Default")
      (node (ref "C10") (pin "2") (pinfunction "2_2") (pintype "power_in"))
      (node (ref "R14") (pin "1") (pinfunction "1_1") (pintype "passive"))
      (node (ref "R15") (pin "2") (pinfunction "2_2") (pintype "passive"))
      (node (ref "U3") (pin "1") (pinfunction "PB5_(MOSI)_1") (pintype "passive"))
    )
    (net (code "28") (name "/OSC1") (class "Default")
      (node (ref "C21") (pin "1") (pinfunction "1_1") (pintype "power_in"))
      (node (ref "R19") (pin "2") (pinfunction "2_2") (pintype "passive"))
      (node (ref "U3") (pin "8") (pinfunction "XTAL1_8") (pintype "passive"))
      (node (ref "Y1") (pin "1") (pinfunction "1_1") (pintype "passive"))
    )
    (net (code "29") (name "/OSC2") (class "Default")
      (node (ref "C20") (pin "1") (pinfunction "1_1") (pintype "power_in"))
      (node (ref "R19") (pin "1") (pinfunction "1_1") (pintype "passive"))
      (node (ref "U3") (pin "7") (pinfunction "XTAL2_7") (pintype "passive"))
      (node (ref "Y1") (pin "2") (pinfunction "2_2") (pintype "passive"))
    )
    (net (code "30") (name "/OVERTEMP_LED") (class "Default")
      (node (ref "C3") (pin "1") (pinfunction "1_1") (pintype "power_in"))
      (node (ref "R22") (pin "1") (pinfunction "1_1") (pintype "passive"))
      (node (ref "R28") (pin "1") (pinfunction "1_1") (pintype "passive"))
      (node (ref "R5") (pin "1") (pinfunction "1_1") (pintype "passive"))
    )
    (net (code "31") (name "/OVERTEMP_LED_UC") (class "Default")
      (node (ref "D8") (pin "3") (pintype "passive"))
      (node (ref "R28") (pin "2") (pinfunction "2_2") (pintype "passive"))
      (node (ref "TP2") (pin "1") (pinfunction "1_1") (pintype "passive"))
      (node (ref "U3") (pin "19") (pinfunction "PC0_(SCL)_19") (pintype "passive"))
    )
    (net (code "32") (name "/POWER_LED") (class "Default")
      (node (ref "C4") (pin "1") (pinfunction "1_1") (pintype "power_in"))
      (node (ref "R31") (pin "1") (pinfunction "1_1") (pintype "passive"))
      (node (ref "R32") (pin "2") (pinfunction "2_2") (pintype "passive"))
      (node (ref "R6") (pin "1") (pinfunction "1_1") (pintype "passive"))
    )
    (net (code "33") (name "/POWER_LED_UC") (class "Default")
      (node (ref "D8") (pin "4") (pintype "passive"))
      (node (ref "R32") (pin "1") (pinfunction "1_1") (pintype "passive"))
      (node (ref "TP8") (pin "1") (pinfunction "1_1") (pintype "passive"))
      (node (ref "U3") (pin "16") (pinfunction "PD7_(OC2)_16") (pintype "passive"))
    )
    (net (code "34") (name "/PROG_MISO") (class "Default")
      (node (ref "ISP") (pin "5") (pinfunction "5_5") (pintype "power_in"))
      (node (ref "R17") (pin "2") (pinfunction "2_2") (pintype "passive"))
    )
    (net (code "35") (name "/PROG_MOSI") (class "Default")
      (node (ref "ISP") (pin "4") (pinfunction "4_4") (pintype "power_in"))
      (node (ref "R14") (pin "2") (pinfunction "2_2") (pintype "passive"))
    )
    (net (code "36") (name "/PROG_SCLK") (class "Default")
      (node (ref "ISP") (pin "3") (pinfunction "3_3") (pintype "power_in"))
      (node (ref "R11") (pin "2") (pinfunction "2_2") (pintype "passive"))
    )
    (net (code "37") (name "/RESET_n") (class "Default")
      (node (ref "R20") (pin "1") (pinfunction "1_1") (pintype "passive"))
      (node (ref "R27") (pin "1") (pinfunction "1_1") (pintype "passive"))
      (node (ref "U3") (pin "4") (pinfunction "nRESET_4") (pintype "passive"))
    )
    (net (code "38") (name "/RSVD_RXD") (class "Default")
      (node (ref "J2") (pin "4") (pinfunction "4_4") (pintype "power_in"))
      (node (ref "R29") (pin "1") (pinfunction "1_1") (pintype "passive"))
      (node (ref "R63") (pin "1") (pinfunction "1_1") (pintype "passive"))
      (node (ref "U3") (pin "9") (pinfunction "PD0_(RXD)_9") (pintype "passive"))
    )
    (net (code "39") (name "/RSVD_TXD") (class "Default")
      (node (ref "J2") (pin "2") (pinfunction "2_2") (pintype "passive"))
      (node (ref "R62") (pin "1") (pinfunction "1_1") (pintype "passive"))
      (node (ref "U3") (pin "10") (pinfunction "PD1_(TXD)_10") (pintype "passive"))
    )
    (net (code "40") (name "/RxD") (class "Default")
      (node (ref "R63") (pin "2") (pinfunction "2_2") (pintype "passive"))
    )
    (net (code "41") (name "/SCLK") (class "Default")
      (node (ref "R11") (pin "1") (pinfunction "1_1") (pintype "passive"))
      (node (ref "R12") (pin "2") (pinfunction "2_2") (pintype "passive"))
      (node (ref "U3") (pin "3") (pinfunction "PB7_(SCK)_3") (pintype "passive"))
    )
    (net (code "42") (name "/SPI_CLK") (class "Default")
      (node (ref "R12") (pin "1") (pinfunction "1_1") (pintype "passive"))
    )
    (net (code "43") (name "/SPI_MISO") (class "Default")
      (node (ref "R18") (pin "1") (pinfunction "1_1") (pintype "passive"))
    )
    (net (code "44") (name "/SPI_MOSI") (class "Default")
      (node (ref "R15") (pin "1") (pinfunction "1_1") (pintype "passive"))
    )
    (net (code "45") (name "/STROBE0_n") (class "Default")
      (node (ref "U3") (pin "24") (pinfunction "PC5_(TDI)_24") (pintype "passive"))
    )
    (net (code "46") (name "/STROBE1_n") (class "Default")
      (node (ref "U3") (pin "25") (pinfunction "PC6_(TOSC1)_25") (pintype "passive"))
    )
    (net (code "47") (name "/STROBE2_n") (class "Default")
      (node (ref "U3") (pin "26") (pinfunction "PC7_(TOSC2)_26") (pintype "passive"))
    )
    (net (code "48") (name "/TxD") (class "Default")
      (node (ref "R62") (pin "2") (pinfunction "2_2") (pintype "passive"))
    )
    (net (code "49") (name "GND") (class "Default")
      (node (ref "C10") (pin "1") (pinfunction "1_1") (pintype "power_in"))
      (node (ref "C13") (pin "1") (pinfunction "1_1") (pintype "power_in"))
      (node (ref "C16") (pin "1") (pinfunction "1_1") (pintype "power_in"))
      (node (ref "C17") (pin "1") (pinfunction "1_1") (pintype "power_in"))
      (node (ref "C20") (pin "2") (pinfunction "2_2") (pintype "power_in"))
      (node (ref "C21") (pin "2") (pinfunction "2_2") (pintype "power_in"))
      (node (ref "C23") (pin "1") (pinfunction "1_1") (pintype "power_in"))
      (node (ref "C24") (pin "1") (pinfunction "1_1") (pintype "power_in"))
      (node (ref "C25") (pin "1") (pinfunction "1_1") (pintype "power_in"))
      (node (ref "C26") (pin "1") (pinfunction "1_1") (pintype "power_in"))
      (node (ref "C27") (pin "1") (pinfunction "1_1") (pintype "power_in"))
      (node (ref "C28") (pin "1") (pinfunction "1_1") (pintype "power_in"))
      (node (ref "C3") (pin "2") (pinfunction "2_2") (pintype "power_in"))
      (node (ref "C4") (pin "2") (pinfunction "2_2") (pintype "power_in"))
      (node (ref "C54") (pin "1") (pinfunction "1_1") (pintype "power_in"))
      (node (ref "C9") (pin "1") (pinfunction "1_1") (pintype "power_in"))
      (node (ref "D10") (pin "1") (pinfunction "1_1") (pintype "passive"))
      (node (ref "D11") (pin "1") (pinfunction "1_1") (pintype "passive"))
      (node (ref "D12") (pin "1") (pinfunction "1_1") (pintype "passive"))
      (node (ref "D13") (pin "1") (pinfunction "1_1") (pintype "passive"))
      (node (ref "D4") (pin "5") (pintype "passive"))
      (node (ref "D4") (pin "6") (pintype "passive"))
      (node (ref "D4") (pin "7") (pintype "passive"))
      (node (ref "D4") (pin "8") (pintype "passive"))
      (node (ref "D8") (pin "5") (pintype "passive"))
      (node (ref "D8") (pin "6") (pintype "passive"))
      (node (ref "D8") (pin "7") (pintype "passive"))
      (node (ref "D8") (pin "8") (pintype "passive"))
      (node (ref "ISP") (pin "6") (pinfunction "6_6") (pintype "power_in"))
      (node (ref "J2") (pin "5") (pinfunction "5_5") (pintype "power_in"))
      (node (ref "J3") (pin "2") (pinfunction "2_2") (pintype "passive"))
      (node (ref "LED3") (pin "2") (pinfunction "C_2") (pintype "passive"))
      (node (ref "LED4") (pin "2") (pinfunction "C_2") (pintype "passive"))
      (node (ref "LED5") (pin "2") (pinfunction "C_2") (pintype "passive"))
      (node (ref "LED6") (pin "2") (pinfunction "C_2") (pintype "passive"))
      (node (ref "R29") (pin "2") (pinfunction "2_2") (pintype "passive"))
      (node (ref "R30") (pin "2") (pinfunction "2_2") (pintype "passive"))
      (node (ref "SW1") (pin "1") (pinfunction "1_1") (pintype "passive"))
      (node (ref "SW2") (pin "1") (pinfunction "1_1") (pintype "passive"))
      (node (ref "SW3") (pin "1") (pinfunction "1_1") (pintype "passive"))
      (node (ref "U2") (pin "1") (pinfunction "GND_1") (pintype "passive"))
      (node (ref "U2") (pin "2") (pinfunction "GND_2") (pintype "passive"))
      (node (ref "U3") (pin "18") (pinfunction "GND_18") (pintype "passive"))
      (node (ref "U3") (pin "28") (pinfunction "GND_28") (pintype "passive"))
      (node (ref "U3") (pin "39") (pinfunction "GND_39") (pintype "passive"))
      (node (ref "U3") (pin "6") (pinfunction "GND_6") (pintype "passive"))
    )
    (net (code "50") (name "Net-(ISP-Pad2)") (class "Default")
      (node (ref "ISP") (pin "2") (pinfunction "2_2") (pintype "passive"))
      (node (ref "R20") (pin "2") (pinfunction "2_2") (pintype "passive"))
    )
    (net (code "51") (name "Net-(J3-Pad1)") (class "Default")
      (node (ref "J3") (pin "1") (pinfunction "1_1") (pintype "passive"))
      (node (ref "R65") (pin "2") (pinfunction "2_2") (pintype "passive"))
    )
    (net (code "52") (name "Net-(LED1-C)") (class "Default")
      (node (ref "LED1") (pin "2") (pinfunction "C_2") (pintype "passive"))
      (node (ref "R5") (pin "2") (pinfunction "2_2") (pintype "passive"))
    )
    (net (code "53") (name "Net-(LED2-C)") (class "Default")
      (node (ref "LED2") (pin "2") (pinfunction "C_2") (pintype "passive"))
      (node (ref "R6") (pin "2") (pinfunction "2_2") (pintype "passive"))
    )
    (net (code "54") (name "Net-(LED3-A)") (class "Default")
      (node (ref "LED3") (pin "1") (pinfunction "A_1") (pintype "passive"))
      (node (ref "R40") (pin "1") (pinfunction "1_1") (pintype "passive"))
    )
    (net (code "55") (name "Net-(LED4-A)") (class "Default")
      (node (ref "LED4") (pin "1") (pinfunction "A_1") (pintype "passive"))
      (node (ref "R41") (pin "1") (pinfunction "1_1") (pintype "passive"))
    )
    (net (code "56") (name "Net-(LED5-A)") (class "Default")
      (node (ref "LED5") (pin "1") (pinfunction "A_1") (pintype "passive"))
      (node (ref "R42") (pin "1") (pinfunction "1_1") (pintype "passive"))
    )
    (net (code "57") (name "Net-(LED6-A)") (class "Default")
      (node (ref "LED6") (pin "1") (pinfunction "A_1") (pintype "passive"))
      (node (ref "R64") (pin "1") (pinfunction "1_1") (pintype "passive"))
    )
    (net (code "58") (name "Net-(U2-SENSE)") (class "Default")
      (node (ref "C25") (pin "2") (pinfunction "2_2") (pintype "power_in"))
      (node (ref "R21") (pin "2") (pinfunction "2_2") (pintype "passive"))
      (node (ref "R30") (pin "1") (pinfunction "1_1") (pintype "passive"))
      (node (ref "SW1") (pin "2") (pinfunction "2_2") (pintype "passive"))
      (node (ref "U2") (pin "5") (pinfunction "SENSE_5") (pintype "passive"))
    )
    (net (code "59") (name "Net-(U2-nRST)") (class "Default")
      (node (ref "C26") (pin "2") (pinfunction "2_2") (pintype "power_in"))
      (node (ref "R23") (pin "2") (pinfunction "2_2") (pintype "passive"))
      (node (ref "R27") (pin "2") (pinfunction "2_2") (pintype "passive"))
      (node (ref "TP5") (pin "1") (pinfunction "1_1") (pintype "passive"))
      (node (ref "U2") (pin "3") (pinfunction "nRST_3") (pintype "passive"))
    )
    (net (code "60") (name "unconnected-(J2-Pad3)") (class "Default")
      (node (ref "J2") (pin "3") (pinfunction "3_3") (pintype "power_in"))
    )
    (net (code "61") (name "unconnected-(U3-PB2_(AIN0{slash}INT2)-Pad42)") (class "Default")
      (node (ref "U3") (pin "42") (pinfunction "PB2_(AIN0/INT2)_42") (pintype "passive+no_connect"))
    )
    (net (code "62") (name "unconnected-(U3-PB3_(AIN1{slash}OC0)-Pad43)") (class "Default")
      (node (ref "U3") (pin "43") (pinfunction "PB3_(AIN1/OC0)_43") (pintype "passive+no_connect"))
    )
    (net (code "63") (name "unconnected-(U3-PB4_(nSS)-Pad44)") (class "Default")
      (node (ref "U3") (pin "44") (pinfunction "PB4_(nSS)_44") (pintype "passive+no_connect"))
    )
    (net (code "64") (name "unconnected-(U3-PC4_(TDO)-Pad23)") (class "Default")
      (node (ref "U3") (pin "23") (pinfunction "PC4_(TDO)_23") (pintype "passive+no_connect"))
    )
  )
)
